# M5StickC_Access_Switch_Input.net
KiCad netlist of a schematic drawn in EAGLE
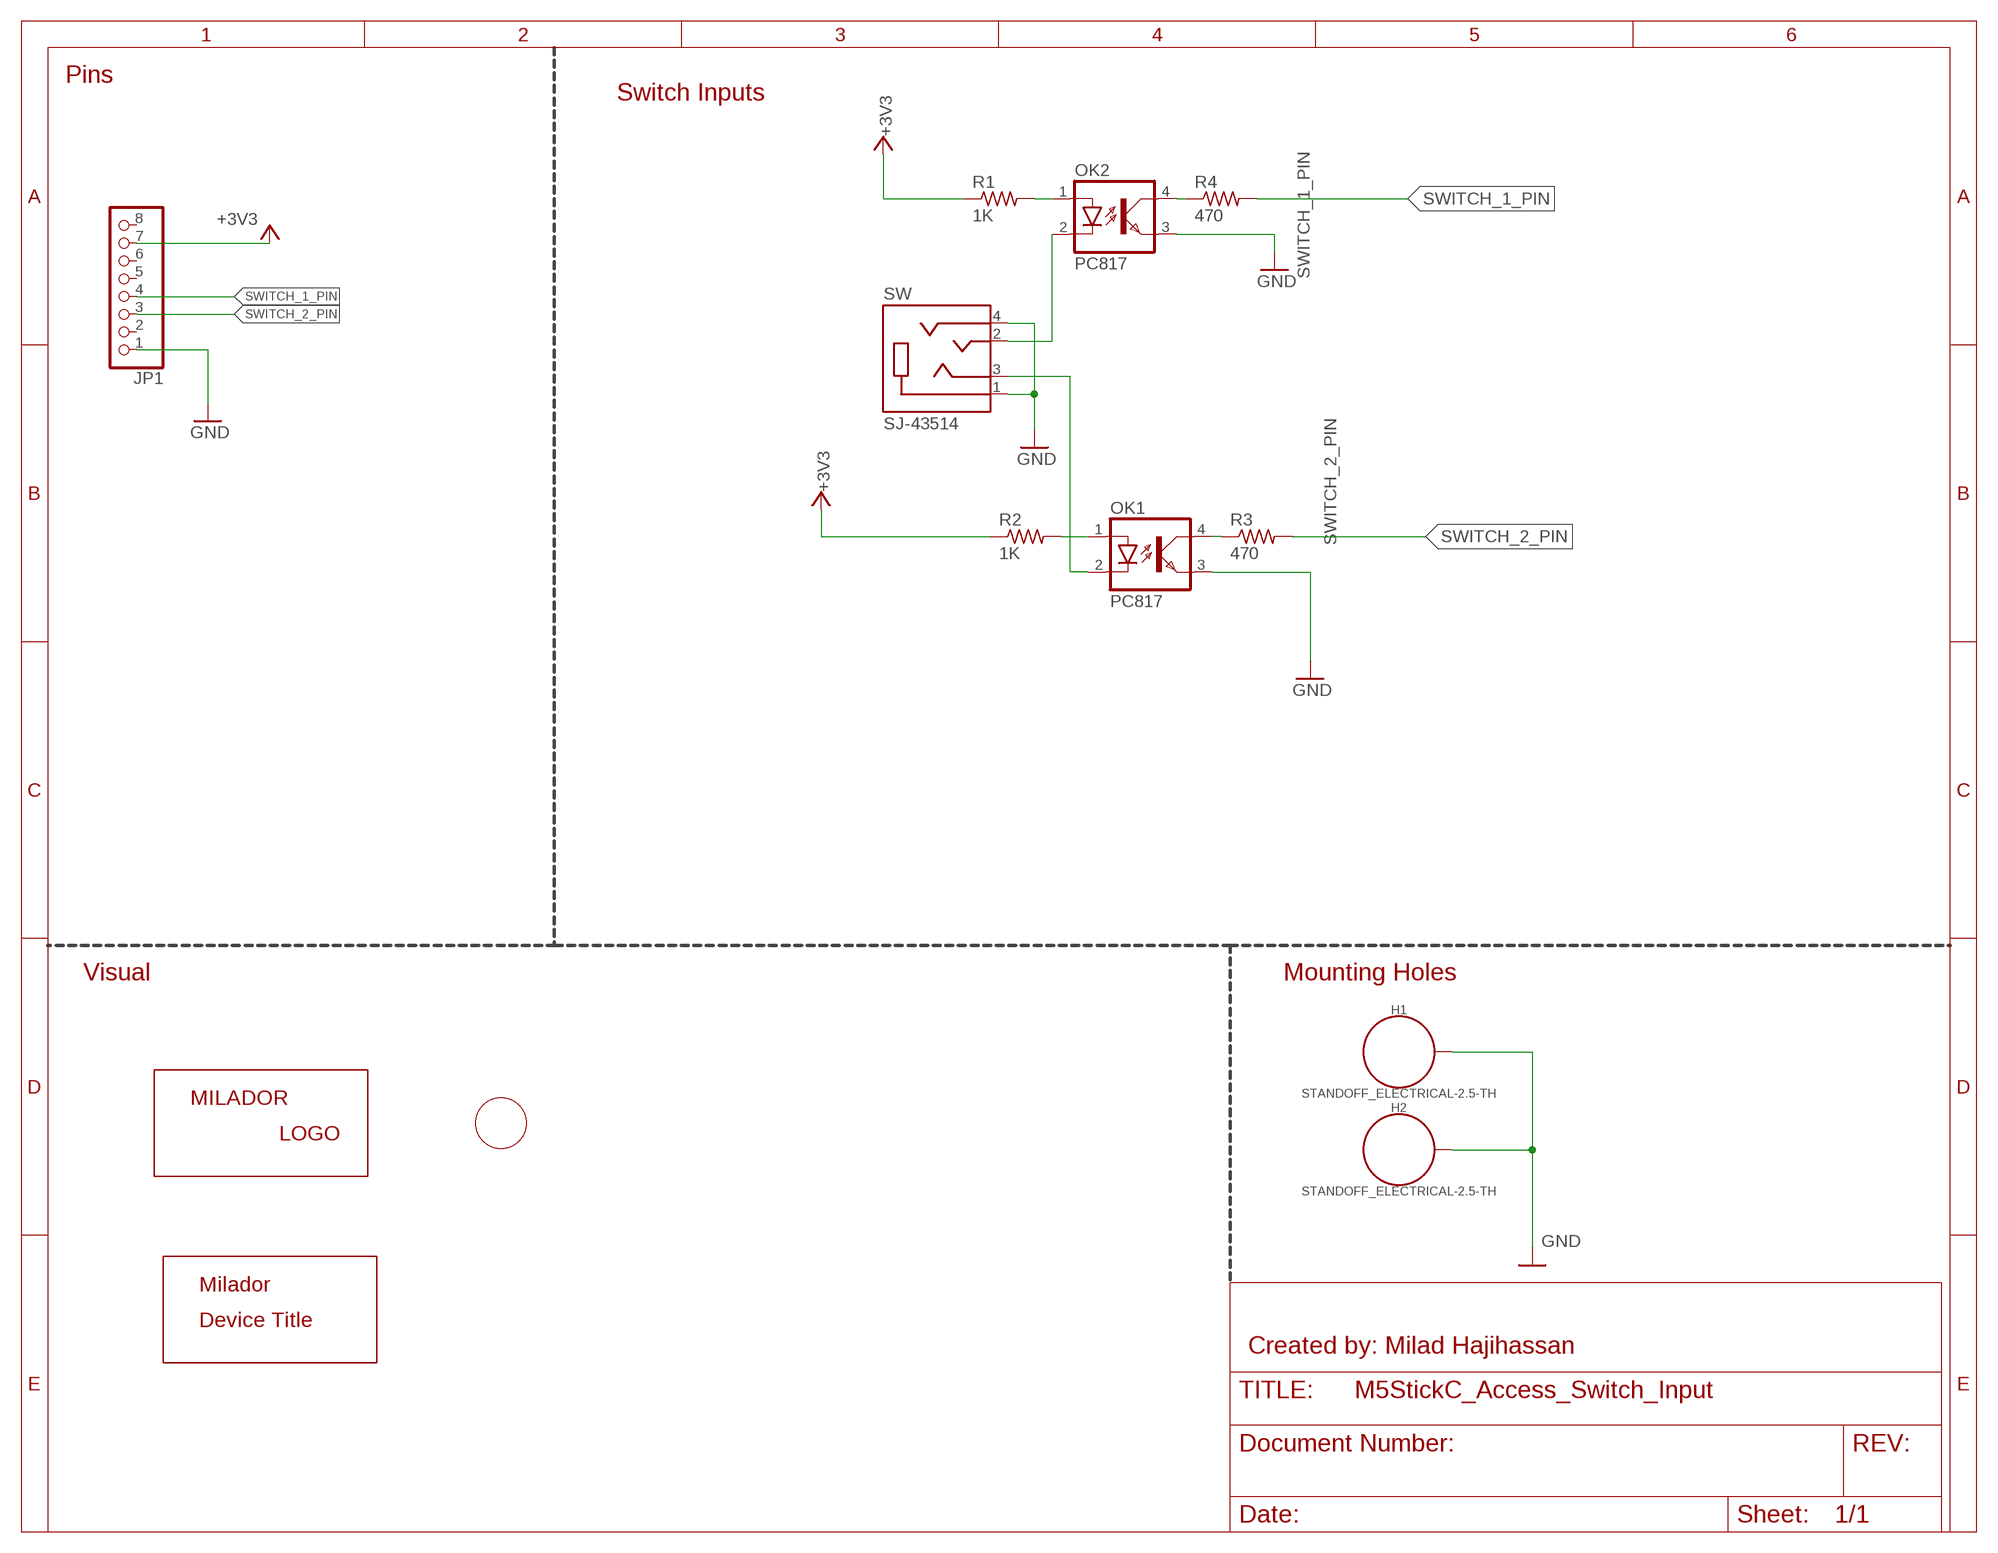
[diagram p0: schematic, sheet 1]

(export (version "E")
  (design (tool "Eeschema 10.0.6"))
  (components
    (comp (ref "H1")
      (value "STANDOFF_ELECTRICAL-2.5-TH")
      (footprint "eagle-import:STANDOFF-ELECTRICAL-2.5-TH")
      (libsource (lib "eagle-import") (part "STANDOFF_ELECTRICAL-2.5-TH"))
    )
    (comp (ref "H2")
      (value "STANDOFF_ELECTRICAL-2.5-TH")
      (footprint "eagle-import:STANDOFF-ELECTRICAL-2.5-TH")
      (libsource (lib "eagle-import") (part "STANDOFF_ELECTRICAL-2.5-TH"))
    )
    (comp (ref "JP1")
      (value "HEADER_MALE-1X8ROUND-RA")
      (footprint "eagle-import:1X08_ROUND_RA")
      (libsource (lib "eagle-import") (part "HEADER_MALE-1X8ROUND-RA"))
    )
    (comp (ref "LABEL_DEVICE_TOP")
      (value "MILADOR-DEVICE-M5-ACCESS-SWITCH")
      (footprint "eagle-import:MILADOR_M5_ACCESS_SWITCH")
      (libsource (lib "eagle-import") (part "MILADOR-DEVICE-M5-ACCESS-SWITCH"))
    )
    (comp (ref "LABEL_INPUT_TOP")
      (value "MILADOR-SWITCH-NAME-SW-INPUT")
      (footprint "eagle-import:SWITCH-INPUT")
      (libsource (lib "eagle-import") (part "MILADOR-SWITCH-NAME-SW-INPUT"))
    )
    (comp (ref "LABEL_LOGO_TOP")
      (value "MILADOR-LOGO-SM")
      (footprint "eagle-import:MILADOR_LOGO2")
      (libsource (lib "eagle-import") (part "MILADOR-LOGO-SM"))
    )
    (comp (ref "OK1")
      (value "PC817")
      (footprint "eagle-import:DIL04")
      (libsource (lib "eagle-import") (part "PC817"))
    )
    (comp (ref "OK2")
      (value "PC817")
      (footprint "eagle-import:DIL04")
      (libsource (lib "eagle-import") (part "PC817"))
    )
    (comp (ref "R1")
      (value "1K")
      (footprint "eagle-import:RESISTOR_0204_5")
      (libsource (lib "eagle-import") (part "RESISTOR-US-0204/5"))
    )
    (comp (ref "R2")
      (value "1K")
      (footprint "eagle-import:RESISTOR_0204_5")
      (libsource (lib "eagle-import") (part "RESISTOR-US-0204/5"))
    )
    (comp (ref "R3")
      (value "470")
      (footprint "eagle-import:RESISTOR_0204_5")
      (libsource (lib "eagle-import") (part "RESISTOR-US-0204/5"))
    )
    (comp (ref "R4")
      (value "470")
      (footprint "eagle-import:RESISTOR_0204_5")
      (libsource (lib "eagle-import") (part "RESISTOR-US-0204/5"))
    )
    (comp (ref "SW")
      (value "SJ-43514")
      (footprint "eagle-import:CUI_SJ-43514")
      (libsource (lib "eagle-import") (part "SJ-43514"))
    )
  )
  (nets
    (net (code "1") (name "+3V3") (class "Default")
      (node (ref "JP1") (pin "7") (pinfunction "7_7") (pintype "passive"))
      (node (ref "R1") (pin "1") (pinfunction "1_1") (pintype "passive"))
      (node (ref "R2") (pin "1") (pinfunction "1_1") (pintype "passive"))
    )
    (net (code "2") (name "GND") (class "Default")
      (node (ref "H1") (pin "P1") (pinfunction "P$1_P1") (pintype "bidirectional"))
      (node (ref "H2") (pin "P1") (pinfunction "P$1_P1") (pintype "bidirectional"))
      (node (ref "JP1") (pin "1") (pinfunction "1_1") (pintype "passive"))
      (node (ref "OK1") (pin "3") (pinfunction "EMIT_3") (pintype "passive"))
      (node (ref "OK2") (pin "3") (pinfunction "EMIT_3") (pintype "passive"))
      (node (ref "SW") (pin "1") (pinfunction "SLEEVE_1") (pintype "passive"))
      (node (ref "SW") (pin "4") (pinfunction "RING2_4") (pintype "passive"))
    )
    (net (code "3") (name "Net-(OK1-A)") (class "Default")
      (node (ref "OK1") (pin "1") (pinfunction "A_1") (pintype "passive"))
      (node (ref "R2") (pin "2") (pinfunction "2_2") (pintype "passive"))
    )
    (net (code "4") (name "Net-(OK1-C)") (class "Default")
      (node (ref "OK1") (pin "2") (pinfunction "C_2") (pintype "passive"))
      (node (ref "SW") (pin "3") (pinfunction "RING1_3") (pintype "passive"))
    )
    (net (code "5") (name "Net-(OK1-COL)") (class "Default")
      (node (ref "OK1") (pin "4") (pinfunction "COL_4") (pintype "passive"))
      (node (ref "R3") (pin "1") (pinfunction "1_1") (pintype "passive"))
    )
    (net (code "6") (name "Net-(OK2-A)") (class "Default")
      (node (ref "OK2") (pin "1") (pinfunction "A_1") (pintype "passive"))
      (node (ref "R1") (pin "2") (pinfunction "2_2") (pintype "passive"))
    )
    (net (code "7") (name "Net-(OK2-C)") (class "Default")
      (node (ref "OK2") (pin "2") (pinfunction "C_2") (pintype "passive"))
      (node (ref "SW") (pin "2") (pinfunction "TIP_2") (pintype "passive"))
    )
    (net (code "8") (name "Net-(OK2-COL)") (class "Default")
      (node (ref "OK2") (pin "4") (pinfunction "COL_4") (pintype "passive"))
      (node (ref "R4") (pin "1") (pinfunction "1_1") (pintype "passive"))
    )
    (net (code "9") (name "SWITCH_1_PIN") (class "Default")
      (node (ref "JP1") (pin "4") (pinfunction "4_4") (pintype "passive"))
      (node (ref "R4") (pin "2") (pinfunction "2_2") (pintype "passive"))
    )
    (net (code "10") (name "SWITCH_2_PIN") (class "Default")
      (node (ref "JP1") (pin "3") (pinfunction "3_3") (pintype "passive"))
      (node (ref "R3") (pin "2") (pinfunction "2_2") (pintype "passive"))
    )
    (net (code "11") (name "unconnected-(JP1-Pad2)") (class "Default")
      (node (ref "JP1") (pin "2") (pinfunction "2_2") (pintype "passive"))
    )
    (net (code "12") (name "unconnected-(JP1-Pad5)") (class "Default")
      (node (ref "JP1") (pin "5") (pinfunction "5_5") (pintype "passive"))
    )
    (net (code "13") (name "unconnected-(JP1-Pad6)") (class "Default")
      (node (ref "JP1") (pin "6") (pinfunction "6_6") (pintype "passive"))
    )
    (net (code "14") (name "unconnected-(JP1-Pad8)") (class "Default")
      (node (ref "JP1") (pin "8") (pinfunction "8_8") (pintype "passive"))
    )
  )
)
